# Sheet2.net
KiCad netlist of a schematic drawn in Altium Designer
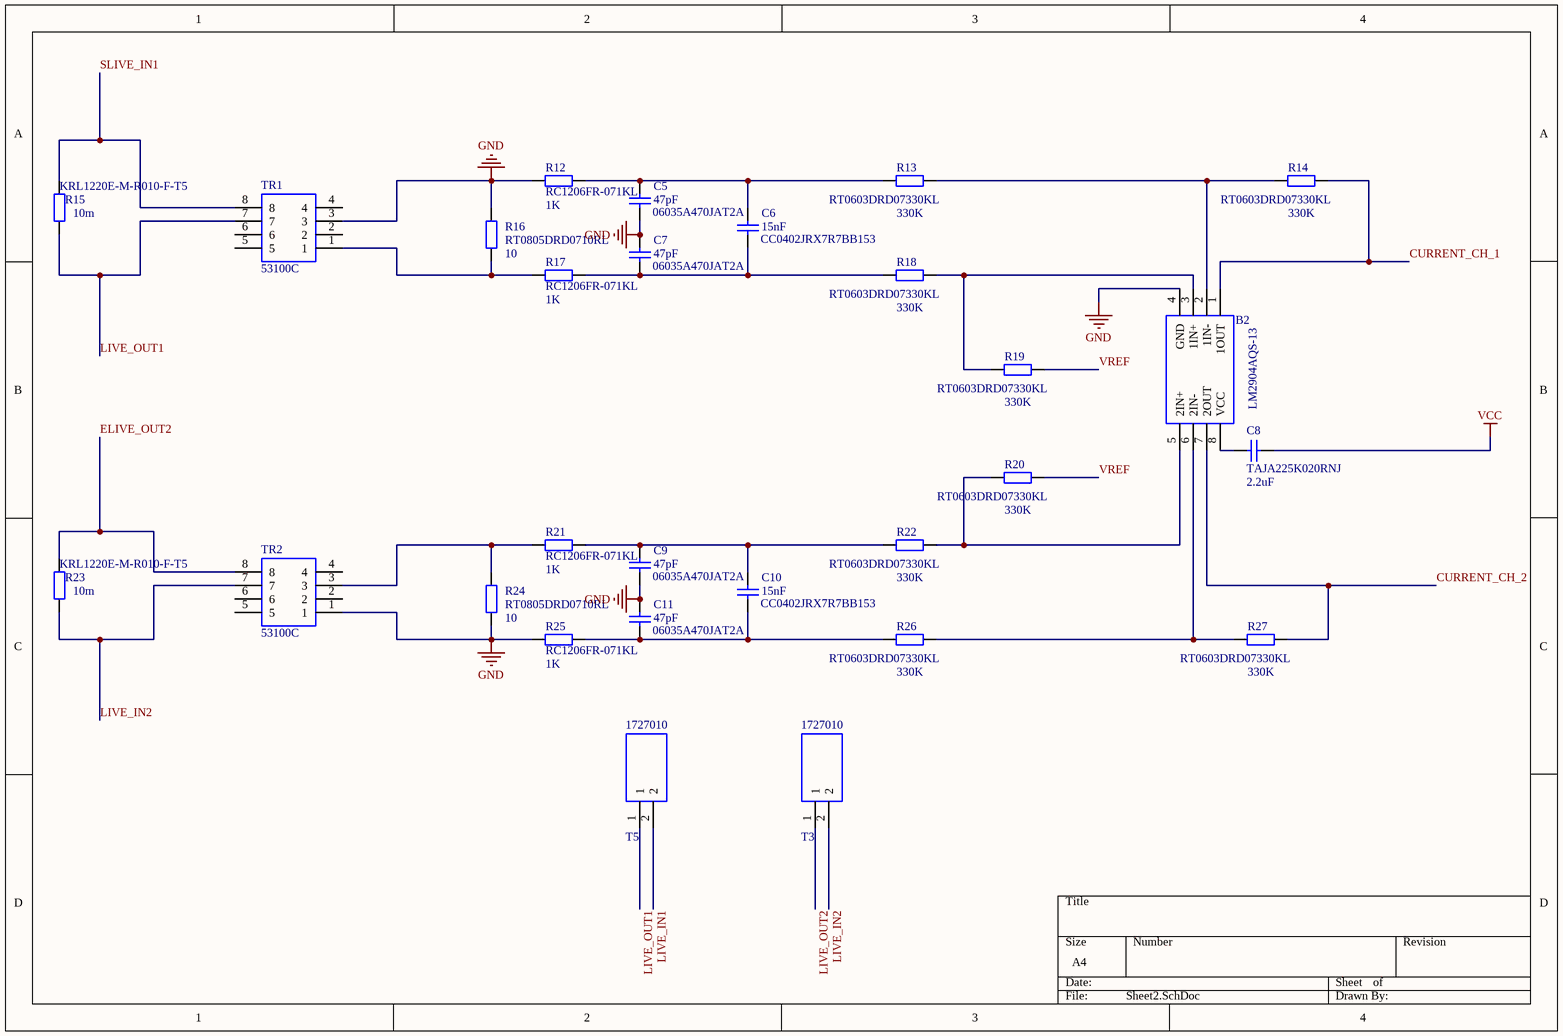
[diagram p0: Sheet2.SchDoc]

(export (version "E")
  (design (tool "Eeschema 10.0.6"))
  (components
    (comp (ref "B2")
      (value "LM2904AQS-13")
      (footprint "SOIC127P600X175-8N:SOIC127P600X175-8N")
      (description "https://www.diodes.com/assets/Datasheets/LM2902_04.pdf")
      (fields (field (name "MANUFACTURER_PART_NUMBER") "LM2904AS-13"))
      (libsource (lib "LM2904AS-13") (part "LM2904AS-13"))
    )
    (comp (ref "C5")
      (value "06035A470JAT2A")
      (footprint "AltiumDesigner:0603-M")
      (description "Capacitor")
      (fields (field (name "ALTIUM_VALUE") "47pF") (field (name "PUBLISHER") "Altium Limited"))
      (libsource (lib "Miscellaneous Devices") (part "Cap"))
    )
    (comp (ref "C6")
      (value "CC0402JRX7R7BB153")
      (footprint "CAPC1005X55N:CAPC1005X55N")
      (description "Capacitor")
      (fields (field (name "ALTIUM_VALUE") "15nF") (field (name "PUBLISHER") "Altium Limited"))
      (libsource (lib "Miscellaneous Devices") (part "Cap"))
    )
    (comp (ref "C7")
      (value "06035A470JAT2A")
      (footprint "AltiumDesigner:0603-M")
      (description "Capacitor")
      (fields (field (name "ALTIUM_VALUE") "47pF") (field (name "PUBLISHER") "Altium Limited"))
      (libsource (lib "Miscellaneous Devices") (part "Cap"))
    )
    (comp (ref "C8")
      (value "TAJA225K020RNJ")
      (footprint "CAPPM3216X180N:CAPPM3216X180N")
      (description "Capacitor")
      (fields (field (name "ALTIUM_VALUE") "2.2uF") (field (name "PUBLISHER") "Altium Limited"))
      (libsource (lib "Miscellaneous Devices") (part "Cap"))
    )
    (comp (ref "C9")
      (value "06035A470JAT2A")
      (footprint "AltiumDesigner:0603-M")
      (description "Capacitor")
      (fields (field (name "ALTIUM_VALUE") "47pF") (field (name "PUBLISHER") "Altium Limited"))
      (libsource (lib "Miscellaneous Devices") (part "Cap"))
    )
    (comp (ref "C10")
      (value "CC0402JRX7R7BB153")
      (footprint "CAPC1005X55N:CAPC1005X55N")
      (description "Capacitor")
      (fields (field (name "ALTIUM_VALUE") "15nF") (field (name "PUBLISHER") "Altium Limited"))
      (libsource (lib "Miscellaneous Devices") (part "Cap"))
    )
    (comp (ref "C11")
      (value "06035A470JAT2A")
      (footprint "AltiumDesigner:0603-M")
      (description "Capacitor")
      (fields (field (name "ALTIUM_VALUE") "47pF") (field (name "PUBLISHER") "Altium Limited"))
      (libsource (lib "Miscellaneous Devices") (part "Cap"))
    )
    (comp (ref "R12")
      (value "RC1206FR-071KL")
      (footprint "AltiumDesigner:RC1206N-M")
      (description "Resistor")
      (fields (field (name "ALTIUM_VALUE") "1K") (field (name "PUBLISHER") "Altium Limited"))
      (libsource (lib "") (part "Res2_2"))
    )
    (comp (ref "R13")
      (value "RT0603DRD07330KL")
      (footprint "AltiumDesigner:RC0603N-M")
      (description "Resistor")
      (fields (field (name "ALTIUM_VALUE") "330K") (field (name "PUBLISHER") "Altium Limited"))
      (libsource (lib "") (part "Res2_1"))
    )
    (comp (ref "R14")
      (value "RT0603DRD07330KL")
      (footprint "AltiumDesigner:RC0603N-M")
      (description "Resistor")
      (fields (field (name "ALTIUM_VALUE") "330K") (field (name "PUBLISHER") "Altium Limited"))
      (libsource (lib "") (part "Res2_1"))
    )
    (comp (ref "R15")
      (value "KRL1220E-M-R010-F-T5")
      (footprint "AltiumDesigner:RES_1220-M")
      (description "Resistor")
      (fields (field (name "ALTIUM_VALUE") "10m") (field (name "PUBLISHER") "Altium Limited"))
      (libsource (lib "Miscellaneous Devices") (part "Res2"))
    )
    (comp (ref "R16")
      (value "RT0805DRD0710RL")
      (footprint "AltiumDesigner:RC0805N-M")
      (description "Resistor")
      (fields (field (name "ALTIUM_VALUE") "10") (field (name "PUBLISHER") "Altium Limited"))
      (libsource (lib "Miscellaneous Devices") (part "Res2"))
    )
    (comp (ref "R17")
      (value "RC1206FR-071KL")
      (footprint "AltiumDesigner:RC1206N-M")
      (description "Resistor")
      (fields (field (name "ALTIUM_VALUE") "1K") (field (name "PUBLISHER") "Altium Limited"))
      (libsource (lib "") (part "Res2_2"))
    )
    (comp (ref "R18")
      (value "RT0603DRD07330KL")
      (footprint "AltiumDesigner:RC0603N-M")
      (description "Resistor")
      (fields (field (name "ALTIUM_VALUE") "330K") (field (name "PUBLISHER") "Altium Limited"))
      (libsource (lib "") (part "Res2_1"))
    )
    (comp (ref "R19")
      (value "RT0603DRD07330KL")
      (footprint "AltiumDesigner:RC0603N-M")
      (description "Resistor")
      (fields (field (name "ALTIUM_VALUE") "330K") (field (name "PUBLISHER") "Altium Limited"))
      (libsource (lib "") (part "Res2_1"))
    )
    (comp (ref "R20")
      (value "RT0603DRD07330KL")
      (footprint "AltiumDesigner:RC0603N-M")
      (description "Resistor")
      (fields (field (name "ALTIUM_VALUE") "330K") (field (name "PUBLISHER") "Altium Limited"))
      (libsource (lib "") (part "Res2_1"))
    )
    (comp (ref "R21")
      (value "RC1206FR-071KL")
      (footprint "AltiumDesigner:RC1206N-M")
      (description "Resistor")
      (fields (field (name "ALTIUM_VALUE") "1K") (field (name "PUBLISHER") "Altium Limited"))
      (libsource (lib "") (part "Res2_2"))
    )
    (comp (ref "R22")
      (value "RT0603DRD07330KL")
      (footprint "AltiumDesigner:RC0603N-M")
      (description "Resistor")
      (fields (field (name "ALTIUM_VALUE") "330K") (field (name "PUBLISHER") "Altium Limited"))
      (libsource (lib "") (part "Res2_1"))
    )
    (comp (ref "R23")
      (value "KRL1220E-M-R010-F-T5")
      (footprint "AltiumDesigner:RES_1220-M")
      (description "Resistor")
      (fields (field (name "ALTIUM_VALUE") "10m") (field (name "PUBLISHER") "Altium Limited"))
      (libsource (lib "Miscellaneous Devices") (part "Res2"))
    )
    (comp (ref "R24")
      (value "RT0805DRD0710RL")
      (footprint "AltiumDesigner:RC0805N-M")
      (description "Resistor")
      (fields (field (name "ALTIUM_VALUE") "10") (field (name "PUBLISHER") "Altium Limited"))
      (libsource (lib "Miscellaneous Devices") (part "Res2"))
    )
    (comp (ref "R25")
      (value "RC1206FR-071KL")
      (footprint "AltiumDesigner:RC1206N-M")
      (description "Resistor")
      (fields (field (name "ALTIUM_VALUE") "1K") (field (name "PUBLISHER") "Altium Limited"))
      (libsource (lib "") (part "Res2_2"))
    )
    (comp (ref "R26")
      (value "RT0603DRD07330KL")
      (footprint "AltiumDesigner:RC0603N-M")
      (description "Resistor")
      (fields (field (name "ALTIUM_VALUE") "330K") (field (name "PUBLISHER") "Altium Limited"))
      (libsource (lib "") (part "Res2_1"))
    )
    (comp (ref "R27")
      (value "RT0603DRD07330KL")
      (footprint "AltiumDesigner:RC0603N-M")
      (description "Resistor")
      (fields (field (name "ALTIUM_VALUE") "330K") (field (name "PUBLISHER") "Altium Limited"))
      (libsource (lib "") (part "Res2_1"))
    )
    (comp (ref "T3")
      (value "1727010")
      (footprint "SHDR2W90P0X350_1X2_750X730X850:SHDR2W90P0X350_1X2_750X730X850P")
      (fields (field (name "RS PART NUMBER") "1015384"))
      (libsource (lib "1727010") (part "1727010"))
    )
    (comp (ref "T5")
      (value "1727010")
      (footprint "SHDR2W90P0X350_1X2_750X730X850:SHDR2W90P0X350_1X2_750X730X850P")
      (fields (field (name "RS PART NUMBER") "1015384"))
      (libsource (lib "1727010") (part "1727010"))
    )
    (comp (ref "TR1")
      (value "53100C")
      (footprint "53050C:53050C")
      (fields (field (name "RS PART NUMBER") "7157021P") (field (name "MANUFACTURER_PART_NUMBER") "53050C"))
      (libsource (lib "53050C") (part "53050C"))
    )
    (comp (ref "TR2")
      (value "53100C")
      (footprint "53050C:53050C")
      (fields (field (name "RS PART NUMBER") "7157021P") (field (name "MANUFACTURER_PART_NUMBER") "53050C"))
      (libsource (lib "53050C") (part "53050C"))
    )
  )
  (nets
    (net (code "1") (name "/CURRENT_CH_1") (class "Default")
      (node (ref "B2") (pin "1") (pinfunction "1OUT_1") (pintype "passive"))
      (node (ref "R14") (pin "2") (pinfunction "2_2") (pintype "passive"))
    )
    (net (code "2") (name "/CURRENT_CH_2") (class "Default")
      (node (ref "B2") (pin "7") (pinfunction "2OUT_7") (pintype "passive"))
      (node (ref "R27") (pin "2") (pinfunction "2_2") (pintype "passive"))
    )
    (net (code "3") (name "/ELIVE_OUT2") (class "Default")
      (node (ref "R23") (pin "2") (pinfunction "2_2") (pintype "passive"))
      (node (ref "TR2") (pin "8") (pinfunction "8_8") (pintype "passive"))
    )
    (net (code "4") (name "/LIVE_IN1") (class "Default")
      (node (ref "T5") (pin "2") (pinfunction "2_2") (pintype "passive"))
    )
    (net (code "5") (name "/LIVE_IN2") (class "Default")
      (node (ref "R23") (pin "1") (pinfunction "1_1") (pintype "passive"))
      (node (ref "T3") (pin "2") (pinfunction "2_2") (pintype "passive"))
      (node (ref "TR2") (pin "7") (pinfunction "7_7") (pintype "passive"))
    )
    (net (code "6") (name "/LIVE_OUT1") (class "Default")
      (node (ref "R15") (pin "1") (pinfunction "1_1") (pintype "passive"))
      (node (ref "T5") (pin "1") (pinfunction "1_1") (pintype "passive"))
      (node (ref "TR1") (pin "7") (pinfunction "7_7") (pintype "passive"))
    )
    (net (code "7") (name "/LIVE_OUT2") (class "Default")
      (node (ref "T3") (pin "1") (pinfunction "1_1") (pintype "passive"))
    )
    (net (code "8") (name "/SLIVE_IN1") (class "Default")
      (node (ref "R15") (pin "2") (pinfunction "2_2") (pintype "passive"))
      (node (ref "TR1") (pin "8") (pinfunction "8_8") (pintype "passive"))
    )
    (net (code "9") (name "/VREF") (class "Default")
      (node (ref "R19") (pin "2") (pinfunction "2_2") (pintype "passive"))
      (node (ref "R20") (pin "2") (pinfunction "2_2") (pintype "passive"))
    )
    (net (code "10") (name "GND") (class "Default")
      (node (ref "B2") (pin "4") (pinfunction "GND_4") (pintype "passive"))
      (node (ref "C11") (pin "2") (pinfunction "2_2") (pintype "passive"))
      (node (ref "C5") (pin "1") (pinfunction "1_1") (pintype "passive"))
      (node (ref "C7") (pin "2") (pinfunction "2_2") (pintype "passive"))
      (node (ref "C9") (pin "1") (pinfunction "1_1") (pintype "passive"))
      (node (ref "R12") (pin "2") (pinfunction "2_2") (pintype "passive"))
      (node (ref "R16") (pin "2") (pinfunction "2_2") (pintype "passive"))
      (node (ref "R24") (pin "1") (pinfunction "1_1") (pintype "passive"))
      (node (ref "R25") (pin "2") (pinfunction "2_2") (pintype "passive"))
      (node (ref "TR1") (pin "3") (pinfunction "3_3") (pintype "passive"))
      (node (ref "TR2") (pin "1") (pinfunction "1_1") (pintype "passive"))
    )
    (net (code "11") (name "Net-(B2-1IN+)") (class "Default")
      (node (ref "B2") (pin "3") (pinfunction "1IN+_3") (pintype "passive"))
      (node (ref "R18") (pin "2") (pinfunction "2_2") (pintype "passive"))
      (node (ref "R19") (pin "1") (pinfunction "1_1") (pintype "passive"))
    )
    (net (code "12") (name "Net-(B2-1IN-)") (class "Default")
      (node (ref "B2") (pin "2") (pinfunction "1IN-_2") (pintype "passive"))
      (node (ref "R13") (pin "2") (pinfunction "2_2") (pintype "passive"))
      (node (ref "R14") (pin "1") (pinfunction "1_1") (pintype "passive"))
    )
    (net (code "13") (name "Net-(B2-2IN+)") (class "Default")
      (node (ref "B2") (pin "5") (pinfunction "2IN+_5") (pintype "passive"))
      (node (ref "R20") (pin "1") (pinfunction "1_1") (pintype "passive"))
      (node (ref "R22") (pin "2") (pinfunction "2_2") (pintype "passive"))
    )
    (net (code "14") (name "Net-(B2-2IN-)") (class "Default")
      (node (ref "B2") (pin "6") (pinfunction "2IN-_6") (pintype "passive"))
      (node (ref "R26") (pin "2") (pinfunction "2_2") (pintype "passive"))
      (node (ref "R27") (pin "1") (pinfunction "1_1") (pintype "passive"))
    )
    (net (code "15") (name "Net-(B2-VCC)") (class "Default")
      (node (ref "B2") (pin "8") (pinfunction "VCC_8") (pintype "power_in"))
      (node (ref "C8") (pin "2") (pinfunction "2_2") (pintype "passive"))
    )
    (net (code "16") (name "Net-(C5-Pad2)") (class "Default")
      (node (ref "C5") (pin "2") (pinfunction "2_2") (pintype "passive"))
      (node (ref "C6") (pin "2") (pinfunction "2_2") (pintype "passive"))
      (node (ref "R12") (pin "1") (pinfunction "1_1") (pintype "passive"))
      (node (ref "R13") (pin "1") (pinfunction "1_1") (pintype "passive"))
    )
    (net (code "17") (name "Net-(C6-Pad1)") (class "Default")
      (node (ref "C6") (pin "1") (pinfunction "1_1") (pintype "passive"))
      (node (ref "C7") (pin "1") (pinfunction "1_1") (pintype "passive"))
      (node (ref "R17") (pin "1") (pinfunction "1_1") (pintype "passive"))
      (node (ref "R18") (pin "1") (pinfunction "1_1") (pintype "passive"))
    )
    (net (code "18") (name "Net-(C10-Pad1)") (class "Default")
      (node (ref "C10") (pin "1") (pinfunction "1_1") (pintype "passive"))
      (node (ref "C11") (pin "1") (pinfunction "1_1") (pintype "passive"))
      (node (ref "R25") (pin "1") (pinfunction "1_1") (pintype "passive"))
      (node (ref "R26") (pin "1") (pinfunction "1_1") (pintype "passive"))
    )
    (net (code "19") (name "Net-(C10-Pad2)") (class "Default")
      (node (ref "C10") (pin "2") (pinfunction "2_2") (pintype "passive"))
      (node (ref "C9") (pin "2") (pinfunction "2_2") (pintype "passive"))
      (node (ref "R21") (pin "1") (pinfunction "1_1") (pintype "passive"))
      (node (ref "R22") (pin "1") (pinfunction "1_1") (pintype "passive"))
    )
    (net (code "20") (name "Net-(R16-Pad1)") (class "Default")
      (node (ref "R16") (pin "1") (pinfunction "1_1") (pintype "passive"))
      (node (ref "R17") (pin "2") (pinfunction "2_2") (pintype "passive"))
      (node (ref "TR1") (pin "1") (pinfunction "1_1") (pintype "passive"))
    )
    (net (code "21") (name "Net-(R21-Pad2)") (class "Default")
      (node (ref "R21") (pin "2") (pinfunction "2_2") (pintype "passive"))
      (node (ref "R24") (pin "2") (pinfunction "2_2") (pintype "passive"))
      (node (ref "TR2") (pin "3") (pinfunction "3_3") (pintype "passive"))
    )
    (net (code "22") (name "VCC") (class "Default")
      (node (ref "C8") (pin "1") (pinfunction "1_1") (pintype "passive"))
    )
    (net (code "23") (name "unconnected-(TR1-Pad2)") (class "Default")
      (node (ref "TR1") (pin "2") (pinfunction "2_2") (pintype "passive"))
    )
    (net (code "24") (name "unconnected-(TR1-Pad4)") (class "Default")
      (node (ref "TR1") (pin "4") (pinfunction "4_4") (pintype "passive"))
    )
    (net (code "25") (name "unconnected-(TR1-Pad5)") (class "Default")
      (node (ref "TR1") (pin "5") (pinfunction "5_5") (pintype "passive"))
    )
    (net (code "26") (name "unconnected-(TR1-Pad6)") (class "Default")
      (node (ref "TR1") (pin "6") (pinfunction "6_6") (pintype "passive"))
    )
    (net (code "27") (name "unconnected-(TR2-Pad2)") (class "Default")
      (node (ref "TR2") (pin "2") (pinfunction "2_2") (pintype "passive"))
    )
    (net (code "28") (name "unconnected-(TR2-Pad4)") (class "Default")
      (node (ref "TR2") (pin "4") (pinfunction "4_4") (pintype "passive"))
    )
    (net (code "29") (name "unconnected-(TR2-Pad5)") (class "Default")
      (node (ref "TR2") (pin "5") (pinfunction "5_5") (pintype "passive"))
    )
    (net (code "30") (name "unconnected-(TR2-Pad6)") (class "Default")
      (node (ref "TR2") (pin "6") (pinfunction "6_6") (pintype "passive"))
    )
  )
)
